# interface2.net
KiCad netlist of a schematic drawn in Altium Designer
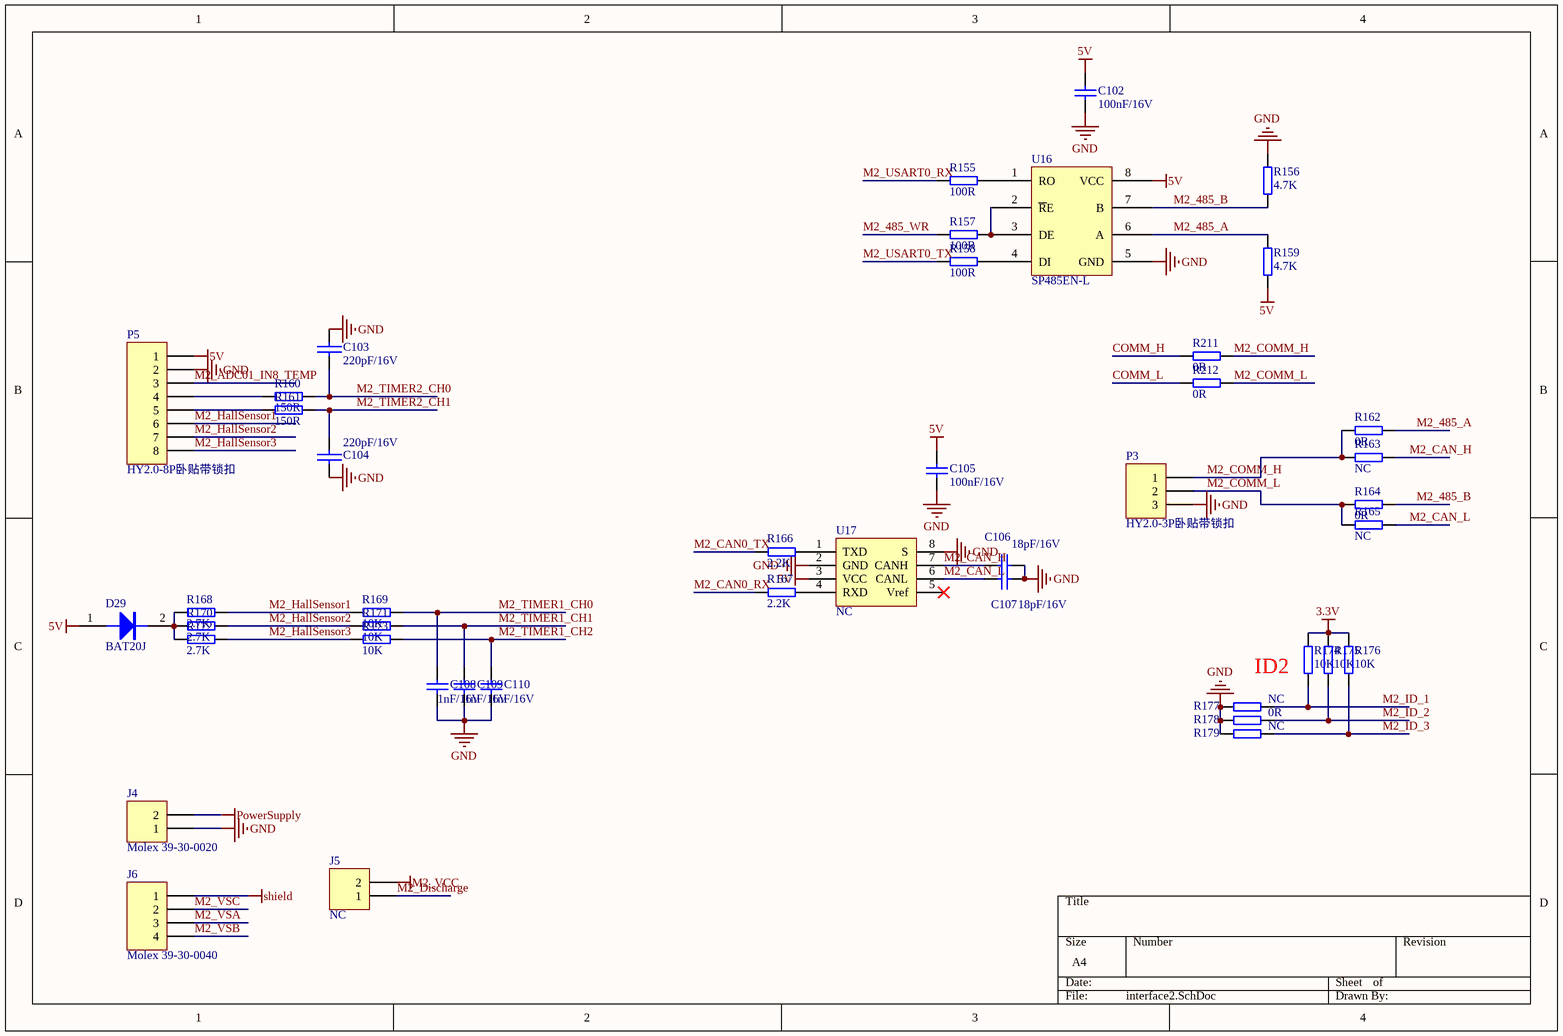
[diagram p0: interface2.SchDoc]

(export (version "E")
  (design (tool "Eeschema 10.0.6"))
  (components
    (comp (ref "C102") (value "100nF/16V") (footprint "C0402") (libsource (lib "zijianku") (part "cap")))
    (comp (ref "C103")
      (value "220pF/16V")
      (footprint "C0402")
      (description "Capacitor")
      (libsource (lib "*") (part "CAP"))
    )
    (comp (ref "C104")
      (value "220pF/16V")
      (footprint "C0402")
      (description "Capacitor")
      (libsource (lib "*") (part "CAP"))
    )
    (comp (ref "C105") (value "100nF/16V") (footprint "C0402") (libsource (lib "zijianku") (part "cap")))
    (comp (ref "C106") (value "18pF/16V") (footprint "C0402") (libsource (lib "zijianku") (part "cap")))
    (comp (ref "C107") (value "18pF/16V") (footprint "C0402") (libsource (lib "zijianku") (part "cap")))
    (comp (ref "C108") (value "1nF/16V") (footprint "C0402") (libsource (lib "zijianku") (part "cap")))
    (comp (ref "C109") (value "1nF/16V") (footprint "C0402") (libsource (lib "zijianku") (part "cap")))
    (comp (ref "C110") (value "1nF/16V") (footprint "C0402") (libsource (lib "zijianku") (part "cap")))
    (comp (ref "D29") (value "BAT20J") (footprint "SOD-323") (libsource (lib "*") (part "DIODE")))
    (comp (ref "J4")
      (value "Molex 39-30-0020")
      (footprint "Molex 39-30-0020")
      (description "Molex型号39-30-0020，使用国产替代")
      (fields (field (name "PUBLISHER") "Altium Limited"))
      (libsource (lib "Common Headers") (part "Header 2"))
    )
    (comp (ref "J5")
      (value "NC")
      (footprint "Molex 39-30-0020")
      (description "Molex型号39-30-0020，使用国产替代")
      (fields (field (name "PUBLISHER") "Altium Limited"))
      (libsource (lib "Common Headers") (part "Header 2"))
    )
    (comp (ref "J6")
      (value "Molex 39-30-0040")
      (footprint "Molex 39-30-0040")
      (description "Molex型号 39-30-0040，使用国产替代")
      (fields (field (name "PUBLISHER") "Altium Limited"))
      (libsource (lib "Common Headers") (part "Header 4"))
    )
    (comp (ref "P3")
      (value "HY2.0-3P卧贴带锁扣")
      (footprint "2.0-3PIN 卧式")
      (fields (field (name "PUBLISHER") "Altium Limited"))
      (libsource (lib "Common Headers") (part "Header 3"))
    )
    (comp (ref "P5")
      (value "HY2.0-8P卧贴带锁扣")
      (footprint "2.0-8PIN 卧式")
      (fields (field (name "PUBLISHER") "Altium Limited"))
      (libsource (lib "Common Headers") (part "Header 8"))
    )
    (comp (ref "R155") (value "100R") (footprint "R0402") (libsource (lib "zijianku") (part "Resistance")))
    (comp (ref "R156") (value "4.7K") (footprint "R0402") (libsource (lib "zijianku") (part "Resistance")))
    (comp (ref "R157") (value "100R") (footprint "R0402") (libsource (lib "zijianku") (part "Resistance")))
    (comp (ref "R158") (value "100R") (footprint "R0402") (libsource (lib "zijianku") (part "Resistance")))
    (comp (ref "R159") (value "4.7K") (footprint "R0402") (libsource (lib "zijianku") (part "Resistance")))
    (comp (ref "R160") (value "150R") (footprint "R0402") (libsource (lib "zijianku") (part "Resistance")))
    (comp (ref "R161") (value "150R") (footprint "R0402") (libsource (lib "zijianku") (part "Resistance")))
    (comp (ref "R162") (value "0R") (footprint "R0603") (libsource (lib "zijianku") (part "Resistance")))
    (comp (ref "R163") (value "NC") (footprint "R0603") (libsource (lib "zijianku") (part "Resistance")))
    (comp (ref "R164") (value "0R") (footprint "R0603") (libsource (lib "zijianku") (part "Resistance")))
    (comp (ref "R165") (value "NC") (footprint "R0603") (libsource (lib "zijianku") (part "Resistance")))
    (comp (ref "R166") (value "2.2K") (footprint "R0402") (libsource (lib "zijianku") (part "Resistance")))
    (comp (ref "R167") (value "2.2K") (footprint "R0402") (libsource (lib "zijianku") (part "Resistance")))
    (comp (ref "R168") (value "2.7K") (footprint "R0402") (libsource (lib "zijianku") (part "Resistance")))
    (comp (ref "R169") (value "10K") (footprint "R0402") (libsource (lib "zijianku") (part "Resistance")))
    (comp (ref "R170") (value "2.7K") (footprint "R0402") (libsource (lib "zijianku") (part "Resistance")))
    (comp (ref "R171") (value "10K") (footprint "R0402") (libsource (lib "zijianku") (part "Resistance")))
    (comp (ref "R172") (value "2.7K") (footprint "R0402") (libsource (lib "zijianku") (part "Resistance")))
    (comp (ref "R173") (value "10K") (footprint "R0402") (libsource (lib "zijianku") (part "Resistance")))
    (comp (ref "R174") (value "10K") (footprint "R0402") (libsource (lib "zijianku") (part "Resistance")))
    (comp (ref "R175") (value "10K") (footprint "R0402") (libsource (lib "zijianku") (part "Resistance")))
    (comp (ref "R176") (value "10K") (footprint "R0402") (libsource (lib "zijianku") (part "Resistance")))
    (comp (ref "R177") (value "NC") (footprint "R0603") (libsource (lib "zijianku") (part "Resistance")))
    (comp (ref "R178") (value "0R") (footprint "R0603") (libsource (lib "zijianku") (part "Resistance")))
    (comp (ref "R179") (value "NC") (footprint "R0603") (libsource (lib "zijianku") (part "Resistance")))
    (comp (ref "R211") (value "0R") (footprint "R0603") (libsource (lib "zijianku") (part "Resistance")))
    (comp (ref "R212") (value "0R") (footprint "R0603") (libsource (lib "zijianku") (part "Resistance")))
    (comp (ref "U16") (value "SP485EN-L") (footprint "SOIC-8") (libsource (lib "zijianku") (part "SP485")))
    (comp (ref "U17")
      (value "NC")
      (footprint "SOIC-8")
      (description "SIT1050T")
      (libsource (lib "Common Device") (part "TJA1050"))
    )
  )
  (nets
    (net (code "1") (name "/COMM_H") (class "Default") (node (ref "R211") (pin "2") (pintype "passive")))
    (net (code "2") (name "/COMM_L") (class "Default") (node (ref "R212") (pin "2") (pintype "passive")))
    (net (code "3") (name "/M2_485_A") (class "Default")
      (node (ref "R159") (pin "2") (pintype "passive"))
      (node (ref "R162") (pin "1") (pintype "passive"))
      (node (ref "U16") (pin "6") (pinfunction "A_6") (pintype "passive"))
    )
    (net (code "4") (name "/M2_485_B") (class "Default")
      (node (ref "R156") (pin "1") (pintype "passive"))
      (node (ref "R164") (pin "1") (pintype "passive"))
      (node (ref "U16") (pin "7") (pinfunction "B_7") (pintype "passive"))
    )
    (net (code "5") (name "/M2_485_WR") (class "Default") (node (ref "R157") (pin "2") (pintype "passive")))
    (net (code "6") (name "/M2_ADC01_IN8_TEMP") (class "Default")
      (node (ref "P5") (pin "3") (pinfunction "3_3") (pintype "passive"))
    )
    (net (code "7") (name "/M2_CAN0_RX") (class "Default") (node (ref "R167") (pin "2") (pintype "passive")))
    (net (code "8") (name "/M2_CAN0_TX") (class "Default") (node (ref "R166") (pin "2") (pintype "passive")))
    (net (code "9") (name "/M2_CAN_H") (class "Default")
      (node (ref "C106") (pin "2") (pinfunction "1_2") (pintype "passive"))
      (node (ref "R163") (pin "1") (pintype "passive"))
      (node (ref "U17") (pin "7") (pinfunction "CANH_7") (pintype "passive"))
    )
    (net (code "10") (name "/M2_CAN_L") (class "Default")
      (node (ref "C107") (pin "2") (pinfunction "1_2") (pintype "passive"))
      (node (ref "R165") (pin "1") (pintype "passive"))
      (node (ref "U17") (pin "6") (pinfunction "CANL_6") (pintype "passive"))
    )
    (net (code "11") (name "/M2_COMM_H") (class "Default")
      (node (ref "P3") (pin "1") (pinfunction "1_1") (pintype "passive"))
      (node (ref "R162") (pin "2") (pintype "passive"))
      (node (ref "R163") (pin "2") (pintype "passive"))
      (node (ref "R211") (pin "1") (pintype "passive"))
    )
    (net (code "12") (name "/M2_COMM_L") (class "Default")
      (node (ref "P3") (pin "2") (pinfunction "2_2") (pintype "passive"))
      (node (ref "R164") (pin "2") (pintype "passive"))
      (node (ref "R165") (pin "2") (pintype "passive"))
      (node (ref "R212") (pin "1") (pintype "passive"))
    )
    (net (code "13") (name "/M2_Discharge") (class "Default")
      (node (ref "J5") (pin "1") (pinfunction "1_1") (pintype "passive"))
    )
    (net (code "14") (name "/M2_HallSensor1") (class "Default")
      (node (ref "P5") (pin "6") (pinfunction "6_6") (pintype "passive"))
      (node (ref "R168") (pin "1") (pintype "passive"))
      (node (ref "R169") (pin "1") (pintype "passive"))
    )
    (net (code "15") (name "/M2_HallSensor2") (class "Default")
      (node (ref "P5") (pin "7") (pinfunction "7_7") (pintype "passive"))
      (node (ref "R170") (pin "1") (pintype "passive"))
      (node (ref "R171") (pin "1") (pintype "passive"))
    )
    (net (code "16") (name "/M2_HallSensor3") (class "Default")
      (node (ref "P5") (pin "8") (pinfunction "8_8") (pintype "passive"))
      (node (ref "R172") (pin "1") (pintype "passive"))
      (node (ref "R173") (pin "1") (pintype "passive"))
    )
    (net (code "17") (name "/M2_ID_1") (class "Default")
      (node (ref "R174") (pin "1") (pintype "passive"))
      (node (ref "R177") (pin "1") (pintype "passive"))
    )
    (net (code "18") (name "/M2_ID_2") (class "Default")
      (node (ref "R175") (pin "1") (pintype "passive"))
      (node (ref "R178") (pin "1") (pintype "passive"))
    )
    (net (code "19") (name "/M2_ID_3") (class "Default")
      (node (ref "R176") (pin "1") (pintype "passive"))
      (node (ref "R179") (pin "1") (pintype "passive"))
    )
    (net (code "20") (name "/M2_TIMER1_CH0") (class "Default")
      (node (ref "C108") (pin "1") (pinfunction "0_1") (pintype "passive"))
      (node (ref "R169") (pin "2") (pintype "passive"))
    )
    (net (code "21") (name "/M2_TIMER1_CH1") (class "Default")
      (node (ref "C109") (pin "1") (pinfunction "0_1") (pintype "passive"))
      (node (ref "R171") (pin "2") (pintype "passive"))
    )
    (net (code "22") (name "/M2_TIMER1_CH2") (class "Default")
      (node (ref "C110") (pin "1") (pinfunction "0_1") (pintype "passive"))
      (node (ref "R173") (pin "2") (pintype "passive"))
    )
    (net (code "23") (name "/M2_TIMER2_CH0") (class "Default")
      (node (ref "C103") (pin "1") (pinfunction "1_1") (pintype "passive"))
      (node (ref "R160") (pin "2") (pintype "passive"))
    )
    (net (code "24") (name "/M2_TIMER2_CH1") (class "Default")
      (node (ref "C104") (pin "2") (pinfunction "2_2") (pintype "passive"))
      (node (ref "R161") (pin "2") (pintype "passive"))
    )
    (net (code "25") (name "/M2_USART0_RX") (class "Default")
      (node (ref "R155") (pin "2") (pintype "passive"))
    )
    (net (code "26") (name "/M2_USART0_TX") (class "Default")
      (node (ref "R158") (pin "2") (pintype "passive"))
    )
    (net (code "27") (name "/M2_VSA") (class "Default")
      (node (ref "J6") (pin "3") (pinfunction "3_3") (pintype "passive"))
    )
    (net (code "28") (name "/M2_VSB") (class "Default")
      (node (ref "J6") (pin "4") (pinfunction "4_4") (pintype "passive"))
    )
    (net (code "29") (name "/M2_VSC") (class "Default")
      (node (ref "J6") (pin "2") (pinfunction "2_2") (pintype "passive"))
    )
    (net (code "30") (name "3.3V") (class "Default")
      (node (ref "R174") (pin "2") (pintype "passive"))
      (node (ref "R175") (pin "2") (pintype "passive"))
      (node (ref "R176") (pin "2") (pintype "passive"))
    )
    (net (code "31") (name "5V") (class "Default")
      (node (ref "C102") (pin "1") (pinfunction "0_1") (pintype "passive"))
      (node (ref "C105") (pin "1") (pinfunction "0_1") (pintype "passive"))
      (node (ref "D29") (pin "1") (pinfunction "A_1") (pintype "passive"))
      (node (ref "P5") (pin "1") (pinfunction "1_1") (pintype "passive"))
      (node (ref "R159") (pin "1") (pintype "passive"))
      (node (ref "U16") (pin "8") (pinfunction "VCC_8") (pintype "passive"))
      (node (ref "U17") (pin "3") (pinfunction "VCC_3") (pintype "passive"))
    )
    (net (code "32") (name "GND") (class "Default")
      (node (ref "C102") (pin "2") (pinfunction "1_2") (pintype "passive"))
      (node (ref "C103") (pin "2") (pinfunction "2_2") (pintype "passive"))
      (node (ref "C104") (pin "1") (pinfunction "1_1") (pintype "passive"))
      (node (ref "C105") (pin "2") (pinfunction "1_2") (pintype "passive"))
      (node (ref "C106") (pin "1") (pinfunction "0_1") (pintype "passive"))
      (node (ref "C107") (pin "1") (pinfunction "0_1") (pintype "passive"))
      (node (ref "C108") (pin "2") (pinfunction "1_2") (pintype "passive"))
      (node (ref "C109") (pin "2") (pinfunction "1_2") (pintype "passive"))
      (node (ref "C110") (pin "2") (pinfunction "1_2") (pintype "passive"))
      (node (ref "J4") (pin "1") (pinfunction "1_1") (pintype "passive"))
      (node (ref "P3") (pin "3") (pinfunction "3_3") (pintype "passive"))
      (node (ref "P5") (pin "2") (pinfunction "2_2") (pintype "passive"))
      (node (ref "R156") (pin "2") (pintype "passive"))
      (node (ref "R177") (pin "2") (pintype "passive"))
      (node (ref "R178") (pin "2") (pintype "passive"))
      (node (ref "R179") (pin "2") (pintype "passive"))
      (node (ref "U16") (pin "5") (pinfunction "GND_5") (pintype "passive"))
      (node (ref "U17") (pin "2") (pinfunction "GND_2") (pintype "passive"))
      (node (ref "U17") (pin "8") (pinfunction "S_8") (pintype "passive"))
    )
    (net (code "33") (name "M2_VCC") (class "Default")
      (node (ref "J5") (pin "2") (pinfunction "2_2") (pintype "passive"))
    )
    (net (code "34") (name "Net-(D29-K)") (class "Default")
      (node (ref "D29") (pin "2") (pinfunction "K_2") (pintype "passive"))
      (node (ref "R168") (pin "2") (pintype "passive"))
      (node (ref "R170") (pin "2") (pintype "passive"))
      (node (ref "R172") (pin "2") (pintype "passive"))
    )
    (net (code "35") (name "Net-(P5-Pad4)") (class "Default")
      (node (ref "P5") (pin "4") (pinfunction "4_4") (pintype "passive"))
      (node (ref "R160") (pin "1") (pintype "passive"))
    )
    (net (code "36") (name "Net-(P5-Pad5)") (class "Default")
      (node (ref "P5") (pin "5") (pinfunction "5_5") (pintype "passive"))
      (node (ref "R161") (pin "1") (pintype "passive"))
    )
    (net (code "37") (name "Net-(U16-DE)") (class "Default")
      (node (ref "R157") (pin "1") (pintype "passive"))
      (node (ref "U16") (pin "2") (pinfunction "~{R}E_2") (pintype "passive"))
      (node (ref "U16") (pin "3") (pinfunction "DE_3") (pintype "passive"))
    )
    (net (code "38") (name "Net-(U16-DI)") (class "Default")
      (node (ref "R158") (pin "1") (pintype "passive"))
      (node (ref "U16") (pin "4") (pinfunction "DI_4") (pintype "passive"))
    )
    (net (code "39") (name "Net-(U16-RO)") (class "Default")
      (node (ref "R155") (pin "1") (pintype "passive"))
      (node (ref "U16") (pin "1") (pinfunction "RO_1") (pintype "passive"))
    )
    (net (code "40") (name "Net-(U17-RXD)") (class "Default")
      (node (ref "R167") (pin "1") (pintype "passive"))
      (node (ref "U17") (pin "4") (pinfunction "RXD_4") (pintype "passive"))
    )
    (net (code "41") (name "Net-(U17-TXD)") (class "Default")
      (node (ref "R166") (pin "1") (pintype "passive"))
      (node (ref "U17") (pin "1") (pinfunction "TXD_1") (pintype "passive"))
    )
    (net (code "42") (name "PowerSupply") (class "Default")
      (node (ref "J4") (pin "2") (pinfunction "2_2") (pintype "passive"))
    )
    (net (code "43") (name "shield") (class "Default")
      (node (ref "J6") (pin "1") (pinfunction "1_1") (pintype "passive"))
    )
    (net (code "44") (name "unconnected-(U17-Vref-Pad5)") (class "Default")
      (node (ref "U17") (pin "5") (pinfunction "Vref_5") (pintype "passive+no_connect"))
    )
  )
)
